# Power-SMPS.net
KiCad netlist of a schematic drawn in Altium Designer
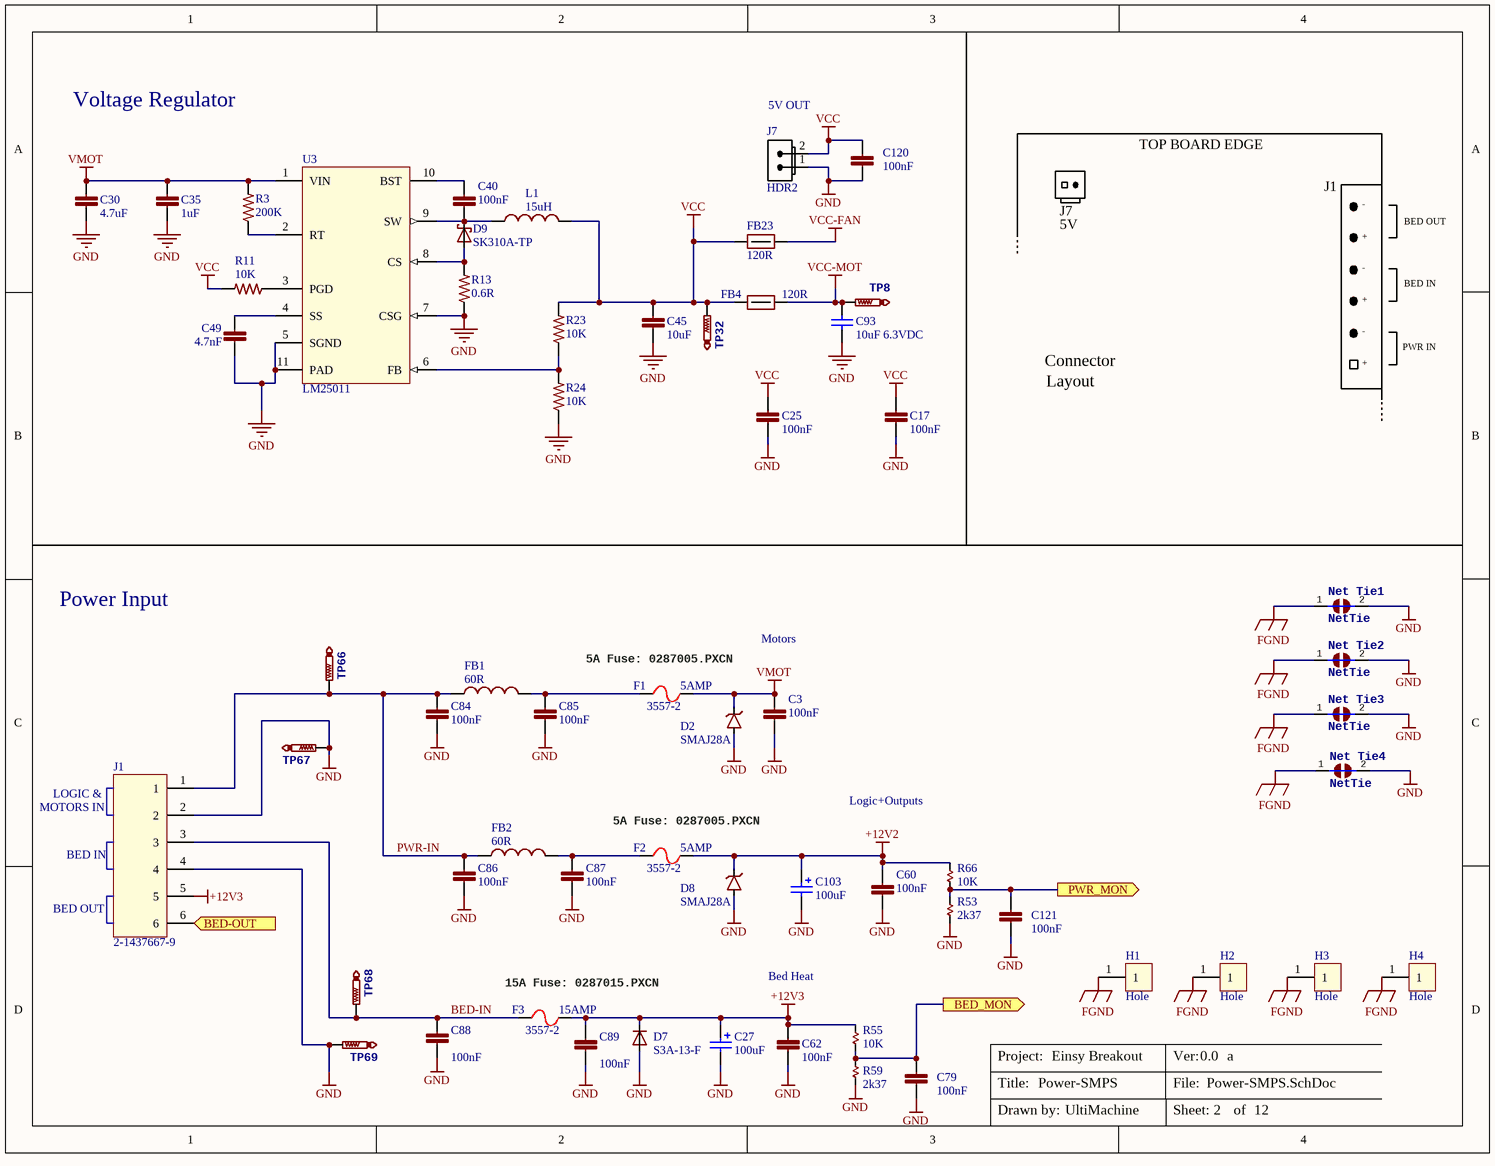
[diagram p0: Power-SMPS.SchDoc]

(export (version "E")
  (design (tool "Eeschema 10.0.6"))
  (components
    (comp (ref "C3")
      (value "100nF")
      (footprint "C0603")
      (description "CAP CER 0603 100nF 50V 10% X7R")
      (fields (field (name "MANUFACTURER") "Kemet") (field (name "TOLERANCE") "+/- 10%"))
      (libsource (lib "3Delight") (part "C0603C104K5RACTU"))
    )
    (comp (ref "C17")
      (value "100nF")
      (footprint "C0402")
      (description "CAP CER 0402 100nF 16V 10% X7R")
      (fields (field (name "MANUFACTURER") "Murata") (field (name "TOLERANCE") "+/- 10%"))
      (libsource (lib "") (part "GRM155R71C104KA88D_2"))
    )
    (comp (ref "C25")
      (value "100nF")
      (footprint "C0603")
      (description "CAP CER 0603 100nF 50V 10% X7R")
      (fields (field (name "MANUFACTURER") "Kemet") (field (name "TOLERANCE") "+/- 10%"))
      (libsource (lib "3Delight") (part "C0603C104K5RACTU"))
    )
    (comp (ref "C27")
      (value "100uF")
      (footprint "CAP-ELEC-063063077")
      (description "CAP ALUM 100UF 35V 20% SMD")
      (fields (field (name "MANUFACTURER") "Nichicon") (field (name "TOLERANCE") "+/- 20%"))
      (libsource (lib "3Delight") (part "UWT1V101MCL1GS"))
    )
    (comp (ref "C30")
      (value "4.7uF")
      (footprint "C1206")
      (description "CAP CER 1206 4.7uF 50V 10% X5R")
      (fields (field (name "MANUFACTURER") "Kemet") (field (name "TOLERANCE") "+/- 10%"))
      (libsource (lib "3Delight") (part "C1206C475K5PACTU"))
    )
    (comp (ref "C35")
      (value "1uF")
      (footprint "C0805")
      (description "CAP CER 0805 1uF 50V 10% X7R")
      (fields (field (name "MANUFACTURER") "Murata") (field (name "TOLERANCE") "+/- 10%"))
      (libsource (lib "3Delight") (part "GRM21BR71H105KA12L"))
    )
    (comp (ref "C40")
      (value "100nF")
      (footprint "C0603")
      (description "CAP CER 0603 100nF 50V 10% X7R")
      (fields (field (name "MANUFACTURER") "Kemet") (field (name "TOLERANCE") "+/- 10%"))
      (libsource (lib "3Delight") (part "C0603C104K5RACTU"))
    )
    (comp (ref "C45")
      (value "10uF")
      (footprint "C0805")
      (description "CAP CER 0805 10uF 10V 10% X5R")
      (fields (field (name "MANUFACTURER") "Kemet") (field (name "TOLERANCE") "+/- 10%"))
      (libsource (lib "3Delight") (part "C0805C106K8PACTU"))
    )
    (comp (ref "C49")
      (value "4.7nF")
      (footprint "C0402")
      (description "CAP CER 0402 4.7nF 25V 10% X7R")
      (fields (field (name "MANUFACTURER") "YAGEO") (field (name "TOLERANCE") "+/- 10%"))
      (libsource (lib "3Delight") (part "CC0402KRX7R8BB472"))
    )
    (comp (ref "C60")
      (value "100nF")
      (footprint "C0603")
      (description "CAP CER 0603 100nF 50V 10% X7R")
      (fields (field (name "MANUFACTURER") "Kemet") (field (name "TOLERANCE") "+/- 10%"))
      (libsource (lib "3Delight") (part "C0603C104K5RACTU"))
    )
    (comp (ref "C62")
      (value "100nF")
      (footprint "C0603")
      (description "CAP CER 0603 100nF 50V 10% X7R")
      (fields (field (name "MANUFACTURER") "Kemet") (field (name "TOLERANCE") "+/- 10%"))
      (libsource (lib "3Delight") (part "C0603C104K5RACTU"))
    )
    (comp (ref "C79")
      (value "100nF")
      (footprint "C0402")
      (description "CAP CER 0402 100nF 16V 10% X7R")
      (fields (field (name "MANUFACTURER") "Murata") (field (name "TOLERANCE") "+/- 10%"))
      (libsource (lib "3Delight") (part "GRM155R71C104KA88D"))
    )
    (comp (ref "C84")
      (value "100nF")
      (footprint "C0603")
      (description "CAP CER 0603 100nF 50V 10% X7R")
      (fields (field (name "MANUFACTURER") "Kemet") (field (name "TOLERANCE") "+/- 10%"))
      (libsource (lib "3Delight") (part "C0603C104K5RACTU"))
    )
    (comp (ref "C85")
      (value "100nF")
      (footprint "C0603")
      (description "CAP CER 0603 100nF 50V 10% X7R")
      (fields (field (name "MANUFACTURER") "Kemet") (field (name "TOLERANCE") "+/- 10%"))
      (libsource (lib "3Delight") (part "C0603C104K5RACTU"))
    )
    (comp (ref "C86")
      (value "100nF")
      (footprint "C0603")
      (description "CAP CER 0603 100nF 50V 10% X7R")
      (fields (field (name "MANUFACTURER") "Kemet") (field (name "TOLERANCE") "+/- 10%"))
      (libsource (lib "3Delight") (part "C0603C104K5RACTU"))
    )
    (comp (ref "C87")
      (value "100nF")
      (footprint "C0603")
      (description "CAP CER 0603 100nF 50V 10% X7R")
      (fields (field (name "MANUFACTURER") "Kemet") (field (name "TOLERANCE") "+/- 10%"))
      (libsource (lib "3Delight") (part "C0603C104K5RACTU"))
    )
    (comp (ref "C88")
      (value "100nF")
      (footprint "C0603")
      (description "CAP CER 0603 100nF 50V 10% X7R")
      (fields (field (name "MANUFACTURER") "Kemet") (field (name "TOLERANCE") "+/- 10%"))
      (libsource (lib "3Delight") (part "C0603C104K5RACTU"))
    )
    (comp (ref "C89")
      (value "100nF")
      (footprint "C0603")
      (description "CAP CER 0603 100nF 50V 10% X7R")
      (fields (field (name "MANUFACTURER") "Kemet") (field (name "TOLERANCE") "+/- 10%"))
      (libsource (lib "3Delight") (part "C0603C104K5RACTU"))
    )
    (comp (ref "C93")
      (value "10uF 6.3VDC")
      (footprint "C0603")
      (description "CAP CER 10UF 6.3V 10% JB 0603")
      (fields (field (name "TOLERANCE") "+/- 10%") (field (name "MANUFACTURER") "TDK"))
      (libsource (lib "Tigershark3D") (part "C1608JB0J106K080AB"))
    )
    (comp (ref "C103")
      (value "100uF")
      (footprint "CAP-ELEC-063063077")
      (description "CAP ALUM 100UF 35V 20% SMD")
      (fields (field (name "MANUFACTURER") "Nichicon") (field (name "TOLERANCE") "+/- 20%"))
      (libsource (lib "3Delight") (part "UWT1V101MCL1GS"))
    )
    (comp (ref "C120")
      (value "100nF")
      (footprint "C0402")
      (description "CAP CER 0402 100nF 16V 10% X7R")
      (fields (field (name "MANUFACTURER") "Murata") (field (name "TOLERANCE") "+/- 10%"))
      (libsource (lib "") (part "GRM155R71C104KA88D_1"))
    )
    (comp (ref "C121")
      (value "100nF")
      (footprint "C0402")
      (description "CAP CER 0402 100nF 16V 10% X7R")
      (fields (field (name "MANUFACTURER") "Murata") (field (name "TOLERANCE") "+/- 10%"))
      (libsource (lib "3Delight") (part "GRM155R71C104KA88D"))
    )
    (comp (ref "D2")
      (value "SMAJ28A")
      (footprint "SMA-SM")
      (description "TVS DIODE 28VWM 45.4VC SMA")
      (fields (field (name "MANUFACTURER") "Diodes Inc") (field (name "TOLERANCE") "NA"))
      (libsource (lib "Diodes") (part "SMAJ28A"))
    )
    (comp (ref "D7")
      (value "S3A-13-F")
      (footprint "DO-214AB")
      (description "DIODE DO-214AB")
      (fields (field (name "MANUFACTURER") "Diodes Incorporated") (field (name "TOLERANCE") "NA"))
      (libsource (lib "3Delight") (part "S3A-13-F"))
    )
    (comp (ref "D8")
      (value "SMAJ28A")
      (footprint "SMA-SM")
      (description "TVS DIODE 28VWM 45.4VC SMA")
      (fields (field (name "MANUFACTURER") "Diodes Inc") (field (name "TOLERANCE") "NA"))
      (libsource (lib "Diodes") (part "SMAJ28A"))
    )
    (comp (ref "D9")
      (value "SK310A-TP")
      (footprint "SMA-SM")
      (description "DIODE Schottky 3A SMA")
      (fields (field (name "MANUFACTURER") "MCC") (field (name "PART") "SK310A"))
      (libsource (lib "3Delight") (part "SK310A"))
    )
    (comp (ref "F1")
      (value "3557-2")
      (footprint "3557")
      (description "FUSE PTH ATO")
      (fields (field (name "MANUFACTURER") "Keystone") (field (name "PART") "Fuse"))
      (libsource (lib "3Delight") (part "3557-2"))
    )
    (comp (ref "F2")
      (value "3557-2")
      (footprint "3557")
      (description "FUSE PTH ATO")
      (fields (field (name "MANUFACTURER") "Keystone") (field (name "PART") "Fuse"))
      (libsource (lib "3Delight") (part "3557-2"))
    )
    (comp (ref "F3")
      (value "3557-2")
      (footprint "3557")
      (description "FUSE PTH ATO")
      (fields (field (name "MANUFACTURER") "Keystone") (field (name "PART") "Fuse"))
      (libsource (lib "3Delight") (part "3557-2"))
    )
    (comp (ref "FB1")
      (value "60R")
      (footprint "3Delight:L1806")
      (description "FERRITE BEAD 1806 60ohm")
      (fields (field (name "MANUFACTURER") "Murata") (field (name "PART") "60Rf"))
      (libsource (lib "3Delight") (part "BLM41PG600SN1L"))
    )
    (comp (ref "FB2")
      (value "60R")
      (footprint "3Delight:L1806")
      (description "FERRITE BEAD 1806 60ohm")
      (fields (field (name "MANUFACTURER") "Murata") (field (name "PART") "60Rf"))
      (libsource (lib "3Delight") (part "BLM41PG600SN1L"))
    )
    (comp (ref "FB4")
      (value "120R")
      (footprint "FB0603")
      (description "FERRITE BEAD 120 OHM 0603 1LN")
      (fields (field (name "MANUFACTURER") "Samsung") (field (name "PART") "FERRITE 120R 3A 0603"))
      (libsource (lib "3Delight") (part "FERRITE 220R 2.5A 0603"))
    )
    (comp (ref "FB23")
      (value "120R")
      (footprint "FB0603")
      (description "FERRITE BEAD 120 OHM 0603 1LN")
      (fields (field (name "MANUFACTURER") "Samsung") (field (name "PART") "FERRITE 120R 3A 0603"))
      (libsource (lib "Inductors") (part "FERRITE 120R 3A 0603"))
    )
    (comp (ref "H1")
      (value "Hole")
      (footprint "Wave_hole_3x7-singleSided")
      (libsource (lib "3Delight") (part "Hole"))
    )
    (comp (ref "H2")
      (value "Hole")
      (footprint "Wave_hole_3x7-singleSided")
      (libsource (lib "3Delight") (part "Hole"))
    )
    (comp (ref "H3")
      (value "Hole")
      (footprint "Wave_hole_3x7-singleSided")
      (libsource (lib "3Delight") (part "Hole"))
    )
    (comp (ref "H4")
      (value "Hole")
      (footprint "Wave_hole_3x7-singleSided")
      (libsource (lib "3Delight") (part "Hole"))
    )
    (comp (ref "J1")
      (value "2-1437667-9")
      (footprint "CON-Barrier-6-8.26mm")
      (description "CONN BARRIER STRIP 6CIRC 0.325\"")
      (fields (field (name "MANUFACTURER") "TE") (field (name "PART") "6POS"))
      (libsource (lib "3Delight") (part "2-1437667-9"))
    )
    (comp (ref "J7")
      (value "HDR2")
      (footprint "70543-02")
      (description "Connector 2pos")
      (fields (field (name "MANUFACTURER") "Molex") (field (name "PART") "10 Pin Conn"))
      (libsource (lib "Archim_0.4") (part "CONN 2PIN VERT 0.1{dblquote} SHRD LOCKING"))
    )
    (comp (ref "L1")
      (value "15uH")
      (footprint "XAL50xx_VLS6045")
      (description "FIXED IND 15UH 2.5A 98 MOHM SMD")
      (fields (field (name "MANUFACTURER") "TDK") (field (name "TOLERANCE") "+/- 20%"))
      (libsource (lib "3Delight") (part "IND 15uH 2.5A 0.075R"))
    )
    (comp (ref "Net Tie1")
      (value "NetTie")
      (footprint "Net Tie")
      (description "Net Tie")
      (fields (field (name "PUBLISHER") "UltiMachine"))
      (libsource (lib "3Delight") (part "NetTie"))
    )
    (comp (ref "Net Tie2")
      (value "NetTie")
      (footprint "Net Tie")
      (description "Net Tie")
      (fields (field (name "PUBLISHER") "UltiMachine"))
      (libsource (lib "3Delight") (part "NetTie"))
    )
    (comp (ref "Net Tie3")
      (value "NetTie")
      (footprint "Net Tie")
      (description "Net Tie")
      (fields (field (name "PUBLISHER") "UltiMachine"))
      (libsource (lib "3Delight") (part "NetTie"))
    )
    (comp (ref "Net Tie4")
      (value "NetTie")
      (footprint "Net Tie")
      (description "Net Tie")
      (fields (field (name "PUBLISHER") "UltiMachine"))
      (libsource (lib "3Delight") (part "NetTie"))
    )
    (comp (ref "R3")
      (value "200K")
      (footprint "R0402")
      (description "RES 0402 200K")
      (fields (field (name "MANUFACTURER") "Vishay Dale") (field (name "TOLERANCE") "+/- 1%"))
      (libsource (lib "3Delight") (part "CRCW0402200KFKED"))
    )
    (comp (ref "R11")
      (value "10K")
      (footprint "R0402")
      (description "RES SMD 10K OHM 1% 1/16W 0402")
      (fields (field (name "MANUFACTURER") "Yageo") (field (name "PART") "10k 1% 0402"))
      (libsource (lib "3Delight") (part "RC0402FR-0710KP"))
    )
    (comp (ref "R13")
      (value "0.6R")
      (footprint "2512R-0.55")
      (description "RES 0.06 OHM 1W 1% 2512 SMD")
      (fields (field (name "MANUFACTURER") "Yageo") (field (name "TOLERANCE") "1%"))
      (libsource (lib "3Delight") (part "RL2512FK-070R06L"))
    )
    (comp (ref "R23")
      (value "10K")
      (footprint "R0402")
      (description "RES SMD 10K OHM 1% 1/16W 0402")
      (fields (field (name "MANUFACTURER") "Yageo") (field (name "PART") "10k 1% 0402"))
      (libsource (lib "3Delight") (part "RC0402FR-0710KP"))
    )
    (comp (ref "R24")
      (value "10K")
      (footprint "R0402")
      (description "RES SMD 10K OHM 1% 1/16W 0402")
      (fields (field (name "MANUFACTURER") "Yageo") (field (name "PART") "10k 1% 0402"))
      (libsource (lib "3Delight") (part "RC0402FR-0710KP"))
    )
    (comp (ref "R53")
      (value "2k37")
      (footprint "R0402")
      (description "RES SMD 2.37K OHM 1% 1/16W 0402")
      (fields (field (name "MANUFACTURER") "Yageo") (field (name "PART") "2.37k"))
      (libsource (lib "3Delight") (part "RC0402FR-072K37L"))
    )
    (comp (ref "R55")
      (value "10K")
      (footprint "R0402")
      (description "RES SMD 10K OHM 1% 1/16W 0402")
      (fields (field (name "MANUFACTURER") "Yageo") (field (name "PART") "10k 1% 0402"))
      (libsource (lib "Resistors") (part "10k 1% 0402"))
    )
    (comp (ref "R59")
      (value "2k37")
      (footprint "R0402")
      (description "RES SMD 2.37K OHM 1% 1/16W 0402")
      (fields (field (name "MANUFACTURER") "Yageo") (field (name "PART") "2.37k"))
      (libsource (lib "3Delight") (part "RC0402FR-072K37L"))
    )
    (comp (ref "R66")
      (value "10K")
      (footprint "R0402")
      (description "RES SMD 10K OHM 1% 1/16W 0402")
      (fields (field (name "MANUFACTURER") "Yageo") (field (name "PART") "10k 1% 0402"))
      (libsource (lib "Resistors") (part "10k 1% 0402"))
    )
    (comp (ref "TP8")
      (value "TestPoint")
      (footprint "TP1-27")
      (description "Test Point")
      (libsource (lib "") (part "TestPoint_2"))
    )
    (comp (ref "TP32")
      (value "TestPoint")
      (footprint "TP1-27")
      (description "Test Point")
      (libsource (lib "") (part "TestPoint_3"))
    )
    (comp (ref "TP66")
      (value "TestPoint")
      (footprint "TP1-27")
      (description "Test Point")
      (libsource (lib "") (part "TestPoint_1"))
    )
    (comp (ref "TP67")
      (value "TestPoint")
      (footprint "TP1-27")
      (description "Test Point")
      (libsource (lib "3Delight") (part "TestPoint"))
    )
    (comp (ref "TP68")
      (value "TestPoint")
      (footprint "TP1-27")
      (description "Test Point")
      (libsource (lib "") (part "TestPoint_1"))
    )
    (comp (ref "TP69")
      (value "TestPoint")
      (footprint "TP1-27")
      (description "Test Point")
      (libsource (lib "") (part "TestPoint_2"))
    )
    (comp (ref "U3")
      (value "LM25011")
      (footprint "VSSOP10")
      (description "REG BUCK")
      (fields (field (name "MANUFACTURER") "TI") (field (name "TOLERANCE") "NA"))
      (libsource (lib "3Delight") (part "LM25011"))
    )
  )
  (nets
    (net (code "1") (name "+12V2") (class "Default")
      (node (ref "C103") (pin "1") (pinfunction "1_1") (pintype "passive"))
      (node (ref "C60") (pin "1") (pinfunction "1_1") (pintype "passive"))
      (node (ref "D8") (pin "K") (pinfunction "K_K") (pintype "passive"))
      (node (ref "F2") (pin "2") (pinfunction "2_2") (pintype "passive"))
      (node (ref "R66") (pin "2") (pinfunction "2_2") (pintype "passive"))
    )
    (net (code "2") (name "+12V3") (class "Default")
      (node (ref "C27") (pin "1") (pinfunction "1_1") (pintype "passive"))
      (node (ref "C62") (pin "1") (pinfunction "1_1") (pintype "passive"))
      (node (ref "C89") (pin "1") (pinfunction "1_1") (pintype "passive"))
      (node (ref "D7") (pin "C") (pinfunction "C_C") (pintype "passive"))
      (node (ref "F3") (pin "2") (pinfunction "2_2") (pintype "passive"))
      (node (ref "J1") (pin "5") (pinfunction "5_5") (pintype "passive"))
      (node (ref "R55") (pin "2") (pinfunction "2_2") (pintype "passive"))
    )
    (net (code "3") (name "/BED-IN") (class "Default")
      (node (ref "C88") (pin "1") (pinfunction "1_1") (pintype "passive"))
      (node (ref "F3") (pin "1") (pinfunction "1_1") (pintype "passive"))
      (node (ref "J1") (pin "3") (pinfunction "3_3") (pintype "passive"))
      (node (ref "TP68") (pin "TP") (pinfunction "TP_TP") (pintype "passive"))
    )
    (net (code "4") (name "/BED-OUT") (class "Default")
      (node (ref "J1") (pin "6") (pinfunction "6_6") (pintype "passive"))
    )
    (net (code "5") (name "/BED_MON") (class "Default")
      (node (ref "C79") (pin "1") (pinfunction "1_1") (pintype "passive"))
      (node (ref "R55") (pin "1") (pinfunction "1_1") (pintype "passive"))
      (node (ref "R59") (pin "1") (pinfunction "1_1") (pintype "passive"))
    )
    (net (code "6") (name "/PWR-IN") (class "Default")
      (node (ref "C84") (pin "1") (pinfunction "1_1") (pintype "passive"))
      (node (ref "C86") (pin "1") (pinfunction "1_1") (pintype "passive"))
      (node (ref "FB1") (pin "1") (pinfunction "1_1") (pintype "passive"))
      (node (ref "FB2") (pin "1") (pinfunction "1_1") (pintype "passive"))
      (node (ref "J1") (pin "1") (pinfunction "1_1") (pintype "passive"))
      (node (ref "TP66") (pin "TP") (pinfunction "TP_TP") (pintype "passive"))
    )
    (net (code "7") (name "/PWR_MON") (class "Default")
      (node (ref "C121") (pin "1") (pinfunction "1_1") (pintype "passive"))
      (node (ref "R53") (pin "1") (pinfunction "1_1") (pintype "passive"))
      (node (ref "R66") (pin "1") (pinfunction "1_1") (pintype "passive"))
    )
    (net (code "8") (name "FGND") (class "Default")
      (node (ref "H1") (pin "1") (pinfunction "1_1") (pintype "power_in"))
      (node (ref "H2") (pin "1") (pinfunction "1_1") (pintype "power_in"))
      (node (ref "H3") (pin "1") (pinfunction "1_1") (pintype "power_in"))
      (node (ref "H4") (pin "1") (pinfunction "1_1") (pintype "power_in"))
      (node (ref "Net Tie1") (pin "1") (pinfunction "1_1") (pintype "passive"))
      (node (ref "Net Tie2") (pin "1") (pinfunction "1_1") (pintype "passive"))
      (node (ref "Net Tie3") (pin "1") (pinfunction "1_1") (pintype "passive"))
      (node (ref "Net Tie4") (pin "1") (pinfunction "1_1") (pintype "passive"))
    )
    (net (code "9") (name "GND") (class "Default")
      (node (ref "C103") (pin "2") (pinfunction "2_2") (pintype "passive"))
      (node (ref "C120") (pin "1") (pinfunction "1_1") (pintype "passive"))
      (node (ref "C121") (pin "2") (pinfunction "2_2") (pintype "passive"))
      (node (ref "C17") (pin "2") (pinfunction "2_2") (pintype "passive"))
      (node (ref "C25") (pin "2") (pinfunction "2_2") (pintype "passive"))
      (node (ref "C27") (pin "2") (pinfunction "2_2") (pintype "passive"))
      (node (ref "C3") (pin "2") (pinfunction "2_2") (pintype "passive"))
      (node (ref "C30") (pin "2") (pinfunction "2_2") (pintype "passive"))
      (node (ref "C35") (pin "2") (pinfunction "2_2") (pintype "passive"))
      (node (ref "C45") (pin "2") (pinfunction "2_2") (pintype "passive"))
      (node (ref "C49") (pin "2") (pinfunction "2_2") (pintype "passive"))
      (node (ref "C60") (pin "2") (pinfunction "2_2") (pintype "passive"))
      (node (ref "C62") (pin "2") (pinfunction "2_2") (pintype "passive"))
      (node (ref "C79") (pin "2") (pinfunction "2_2") (pintype "passive"))
      (node (ref "C84") (pin "2") (pinfunction "2_2") (pintype "passive"))
      (node (ref "C85") (pin "2") (pinfunction "2_2") (pintype "passive"))
      (node (ref "C86") (pin "2") (pinfunction "2_2") (pintype "passive"))
      (node (ref "C87") (pin "2") (pinfunction "2_2") (pintype "passive"))
      (node (ref "C88") (pin "2") (pinfunction "2_2") (pintype "passive"))
      (node (ref "C89") (pin "2") (pinfunction "2_2") (pintype "passive"))
      (node (ref "C93") (pin "1") (pinfunction "1_1") (pintype "passive"))
      (node (ref "D2") (pin "A") (pinfunction "A_A") (pintype "passive"))
      (node (ref "D7") (pin "A") (pinfunction "A_A") (pintype "passive"))
      (node (ref "D8") (pin "A") (pinfunction "A_A") (pintype "passive"))
      (node (ref "J1") (pin "2") (pinfunction "2_2") (pintype "passive"))
      (node (ref "J1") (pin "4") (pinfunction "4_4") (pintype "passive"))
      (node (ref "J7") (pin "1") (pinfunction "S_1") (pintype "passive"))
      (node (ref "Net Tie1") (pin "2") (pinfunction "2_2") (pintype "passive"))
      (node (ref "Net Tie2") (pin "2") (pinfunction "2_2") (pintype "passive"))
      (node (ref "Net Tie3") (pin "2") (pinfunction "2_2") (pintype "passive"))
      (node (ref "Net Tie4") (pin "2") (pinfunction "2_2") (pintype "passive"))
      (node (ref "R13") (pin "1") (pinfunction "1_1") (pintype "passive"))
      (node (ref "R24") (pin "1") (pinfunction "1_1") (pintype "passive"))
      (node (ref "R53") (pin "2") (pinfunction "2_2") (pintype "passive"))
      (node (ref "R59") (pin "2") (pinfunction "2_2") (pintype "passive"))
      (node (ref "TP67") (pin "TP") (pinfunction "TP_TP") (pintype "passive"))
      (node (ref "TP69") (pin "TP") (pinfunction "TP_TP") (pintype "passive"))
      (node (ref "U3") (pin "11") (pinfunction "PAD_11") (pintype "power_in"))
      (node (ref "U3") (pin "5") (pinfunction "SGND_5") (pintype "power_in"))
      (node (ref "U3") (pin "7") (pinfunction "CSG_7") (pintype "input"))
    )
    (net (code "10") (name "Net-(C85-Pad1)") (class "Default")
      (node (ref "C85") (pin "1") (pinfunction "1_1") (pintype "passive"))
      (node (ref "F1") (pin "1") (pinfunction "1_1") (pintype "passive"))
      (node (ref "FB1") (pin "2") (pinfunction "2_2") (pintype "passive"))
    )
    (net (code "11") (name "Net-(C87-Pad1)") (class "Default")
      (node (ref "C87") (pin "1") (pinfunction "1_1") (pintype "passive"))
      (node (ref "F2") (pin "1") (pinfunction "1_1") (pintype "passive"))
      (node (ref "FB2") (pin "2") (pinfunction "2_2") (pintype "passive"))
    )
    (net (code "12") (name "Net-(U3-BST)") (class "Default")
      (node (ref "C40") (pin "1") (pinfunction "1_1") (pintype "passive"))
      (node (ref "U3") (pin "10") (pinfunction "BST_10") (pintype "power_in"))
    )
    (net (code "13") (name "Net-(U3-CS)") (class "Default")
      (node (ref "D9") (pin "A") (pinfunction "A_A") (pintype "passive"))
      (node (ref "R13") (pin "2") (pinfunction "2_2") (pintype "passive"))
      (node (ref "U3") (pin "8") (pinfunction "CS_8") (pintype "input"))
    )
    (net (code "14") (name "Net-(U3-FB)") (class "Default")
      (node (ref "R23") (pin "1") (pinfunction "1_1") (pintype "passive"))
      (node (ref "R24") (pin "2") (pinfunction "2_2") (pintype "passive"))
      (node (ref "U3") (pin "6") (pinfunction "FB_6") (pintype "input"))
    )
    (net (code "15") (name "Net-(U3-PGD)") (class "Default")
      (node (ref "R11") (pin "1") (pinfunction "1_1") (pintype "passive"))
      (node (ref "U3") (pin "3") (pinfunction "PGD_3") (pintype "power_in"))
    )
    (net (code "16") (name "Net-(U3-RT)") (class "Default")
      (node (ref "R3") (pin "1") (pinfunction "1_1") (pintype "passive"))
      (node (ref "U3") (pin "2") (pinfunction "RT_2") (pintype "power_in"))
    )
    (net (code "17") (name "Net-(U3-SS)") (class "Default")
      (node (ref "C49") (pin "1") (pinfunction "1_1") (pintype "passive"))
      (node (ref "U3") (pin "4") (pinfunction "SS_4") (pintype "power_in"))
    )
    (net (code "18") (name "Net-(U3-SW)") (class "Default")
      (node (ref "C40") (pin "2") (pinfunction "2_2") (pintype "passive"))
      (node (ref "D9") (pin "C") (pinfunction "C_C") (pintype "passive"))
      (node (ref "L1") (pin "1") (pinfunction "1_1") (pintype "passive"))
      (node (ref "U3") (pin "9") (pinfunction "SW_9") (pintype "output"))
    )
    (net (code "19") (name "VCC") (class "Default")
      (node (ref "C120") (pin "2") (pinfunction "2_2") (pintype "passive"))
      (node (ref "C17") (pin "1") (pinfunction "1_1") (pintype "passive"))
      (node (ref "C25") (pin "1") (pinfunction "1_1") (pintype "passive"))
      (node (ref "C45") (pin "1") (pinfunction "1_1") (pintype "passive"))
      (node (ref "FB23") (pin "1") (pinfunction "1_1") (pintype "passive"))
      (node (ref "FB4") (pin "1") (pinfunction "1_1") (pintype "passive"))
      (node (ref "J7") (pin "2") (pinfunction "S_2") (pintype "passive"))
      (node (ref "L1") (pin "2") (pinfunction "2_2") (pintype "passive"))
      (node (ref "R11") (pin "2") (pinfunction "2_2") (pintype "passive"))
      (node (ref "R23") (pin "2") (pinfunction "2_2") (pintype "passive"))
      (node (ref "TP32") (pin "TP") (pinfunction "TP_TP") (pintype "passive"))
    )
    (net (code "20") (name "VCC-FAN") (class "Default")
      (node (ref "FB23") (pin "2") (pinfunction "2_2") (pintype "passive"))
    )
    (net (code "21") (name "VCC-MOT") (class "Default")
      (node (ref "C93") (pin "2") (pinfunction "2_2") (pintype "passive"))
      (node (ref "FB4") (pin "2") (pinfunction "2_2") (pintype "passive"))
      (node (ref "TP8") (pin "TP") (pinfunction "TP_TP") (pintype "passive"))
    )
    (net (code "22") (name "VMOT") (class "Default")
      (node (ref "C3") (pin "1") (pinfunction "1_1") (pintype "passive"))
      (node (ref "C30") (pin "1") (pinfunction "1_1") (pintype "passive"))
      (node (ref "C35") (pin "1") (pinfunction "1_1") (pintype "passive"))
      (node (ref "D2") (pin "K") (pinfunction "K_K") (pintype "passive"))
      (node (ref "F1") (pin "2") (pinfunction "2_2") (pintype "passive"))
      (node (ref "R3") (pin "2") (pinfunction "2_2") (pintype "passive"))
      (node (ref "U3") (pin "1") (pinfunction "VIN_1") (pintype "power_in"))
    )
  )
)
